# lizard-ttl-register-4bit.net
KiCad netlist of a schematic drawn in EAGLE
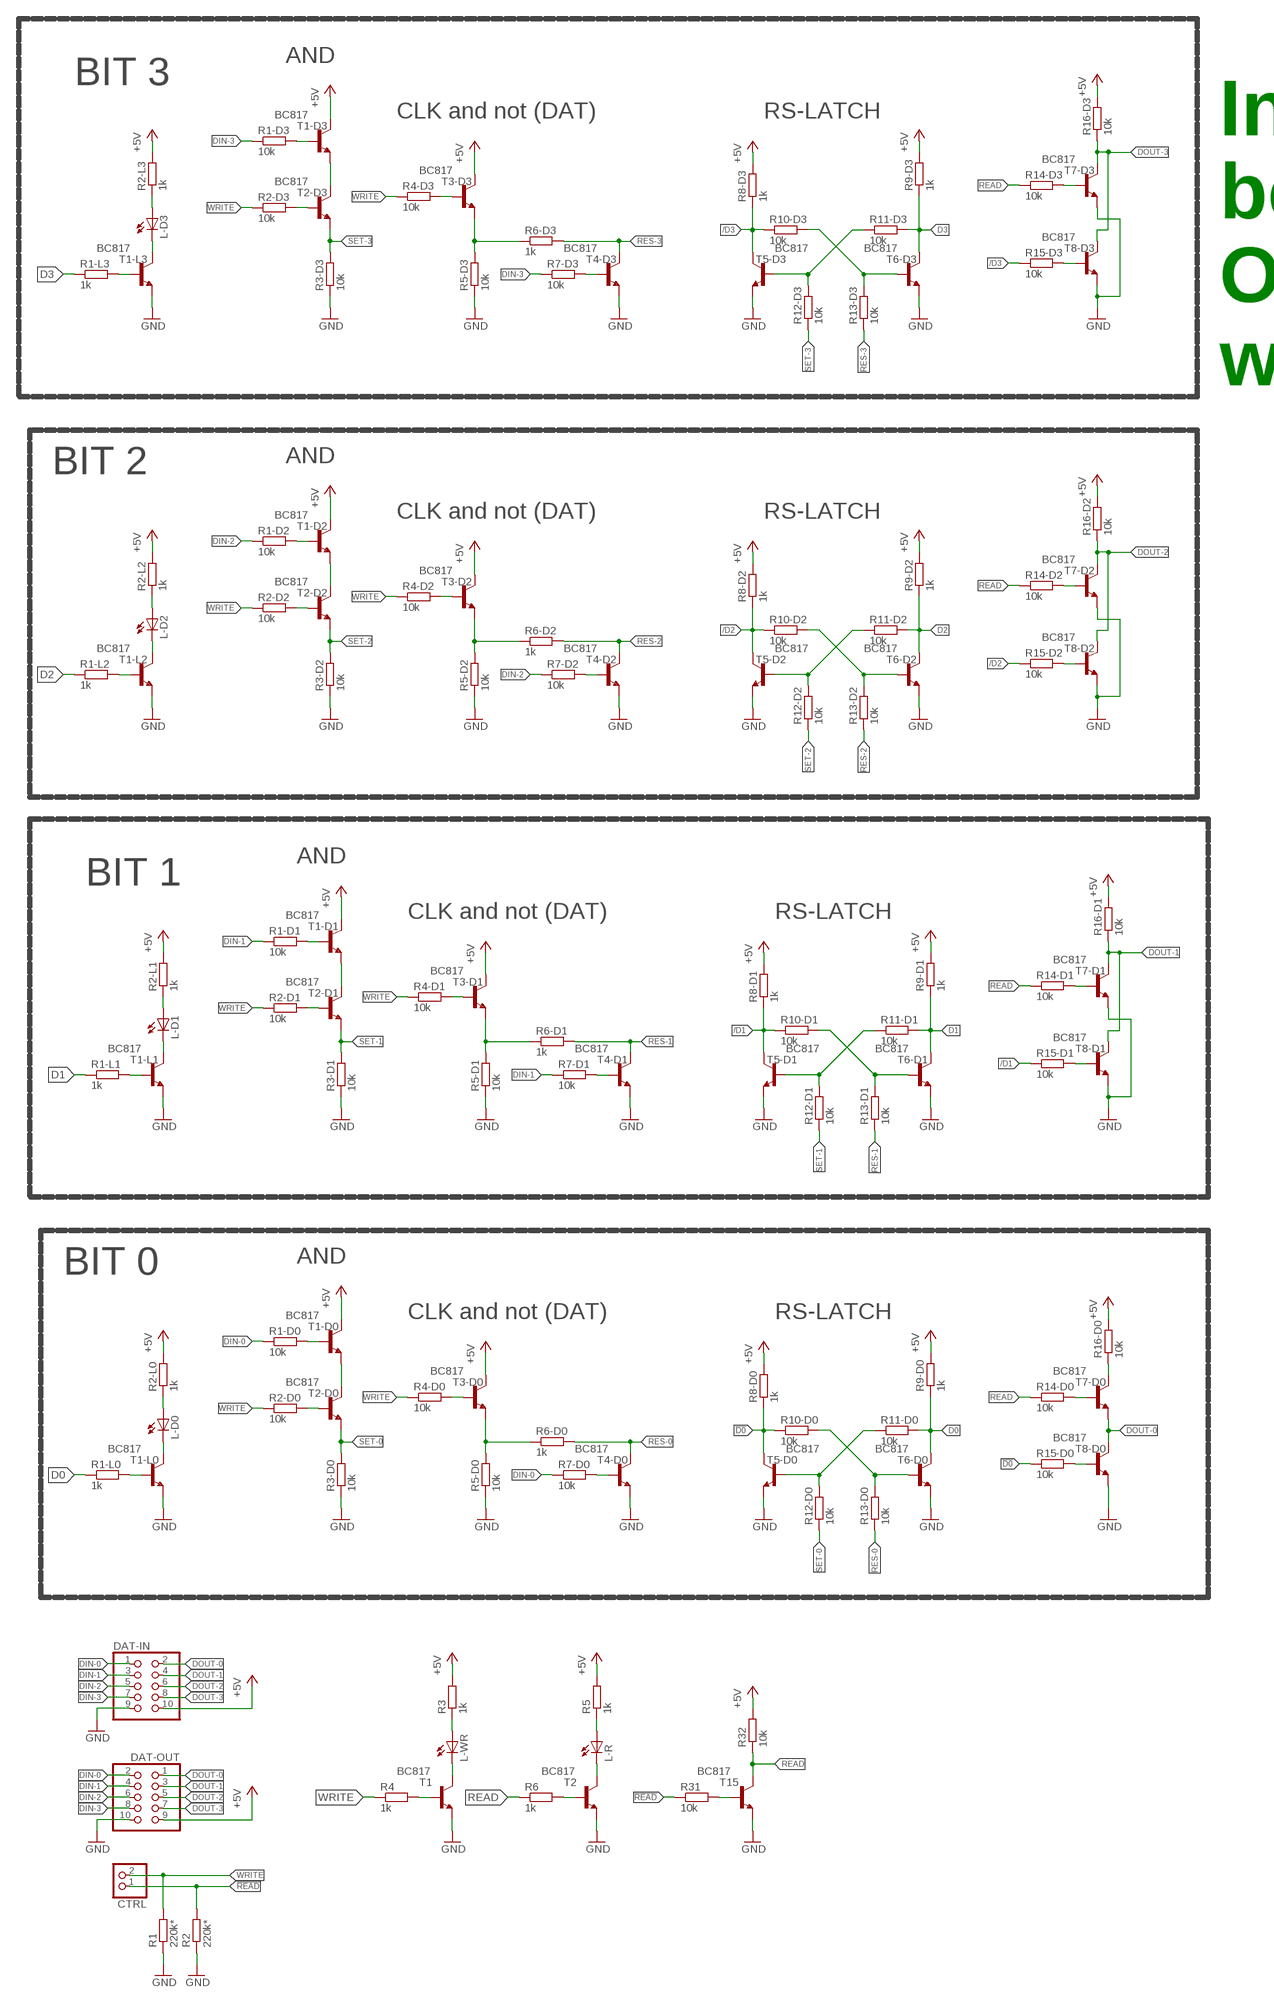
[diagram p0: schematic, sheet 1, part 1 of 2]
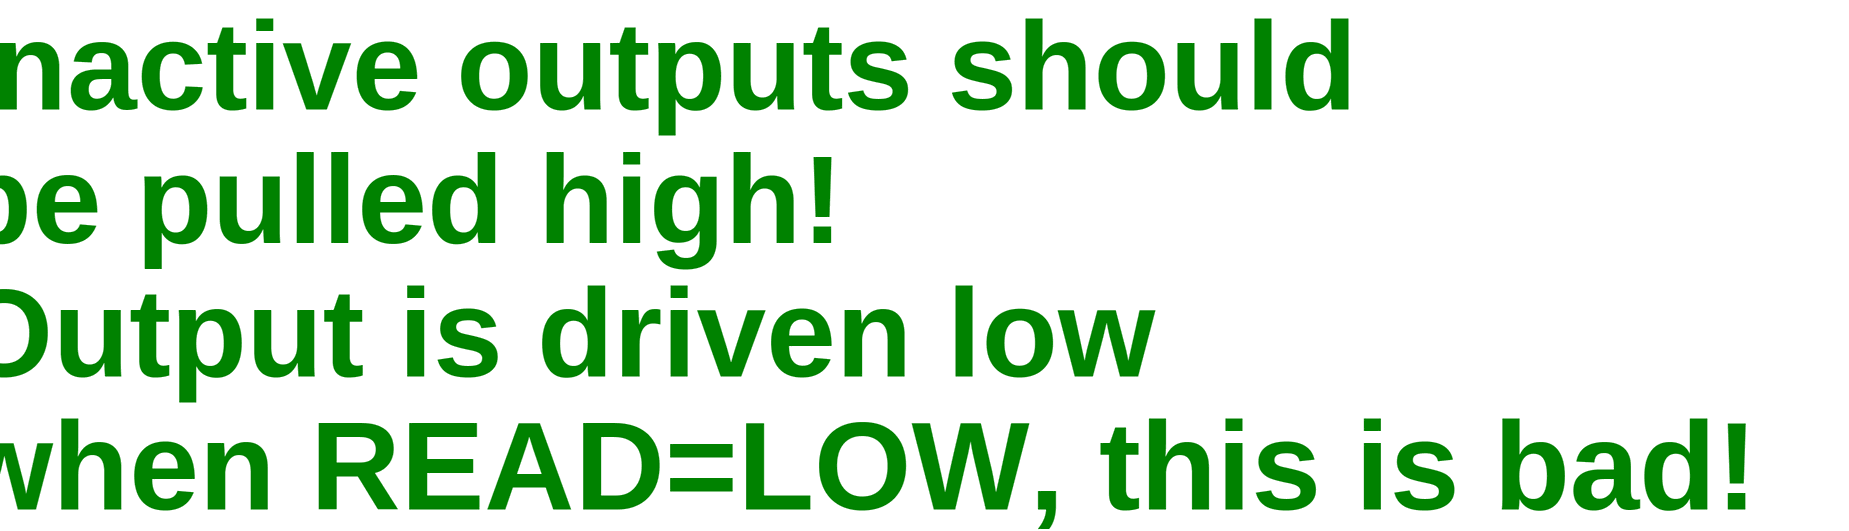
[diagram p1: schematic, sheet 1, part 2 of 2]

(export (version "E")
  (design (tool "Eeschema 10.0.6"))
  (components
    (comp (ref "CTRL")
      (value "PINHD-1X2")
      (footprint "eagle-import:1X02")
      (libsource (lib "eagle-import") (part "PINHD-1X2"))
    )
    (comp (ref "DAT-IN")
      (value "PINHD-2X5EDGE")
      (footprint "eagle-import:2X05_EDGE")
      (libsource (lib "eagle-import") (part "PINHD-2X5EDGE"))
    )
    (comp (ref "DAT-OUT")
      (value "PINHD-2X5EDGE")
      (footprint "eagle-import:2X05_EDGE")
      (libsource (lib "eagle-import") (part "PINHD-2X5EDGE"))
    )
    (comp (ref "L-D0")
      (value "LEDCHIPLED_0603")
      (footprint "eagle-import:CHIPLED_0603")
      (libsource (lib "eagle-import") (part "LEDCHIPLED_0603"))
    )
    (comp (ref "L-D1")
      (value "LEDCHIPLED_0603")
      (footprint "eagle-import:CHIPLED_0603")
      (libsource (lib "eagle-import") (part "LEDCHIPLED_0603"))
    )
    (comp (ref "L-D2")
      (value "LEDCHIPLED_0603")
      (footprint "eagle-import:CHIPLED_0603")
      (libsource (lib "eagle-import") (part "LEDCHIPLED_0603"))
    )
    (comp (ref "L-D3")
      (value "LEDCHIPLED_0603")
      (footprint "eagle-import:CHIPLED_0603")
      (libsource (lib "eagle-import") (part "LEDCHIPLED_0603"))
    )
    (comp (ref "L-R")
      (value "LEDCHIPLED_0603")
      (footprint "eagle-import:CHIPLED_0603")
      (libsource (lib "eagle-import") (part "LEDCHIPLED_0603"))
    )
    (comp (ref "L-WR")
      (value "LEDCHIPLED_0603")
      (footprint "eagle-import:CHIPLED_0603")
      (libsource (lib "eagle-import") (part "LEDCHIPLED_0603"))
    )
    (comp (ref "R1")
      (value "220k*")
      (footprint "eagle-import:R0603")
      (libsource (lib "eagle-import") (part "R-EU_R0603"))
    )
    (comp (ref "R1-D0")
      (value "10k")
      (footprint "eagle-import:R0603")
      (libsource (lib "eagle-import") (part "R-EU_R0603"))
    )
    (comp (ref "R1-D1")
      (value "10k")
      (footprint "eagle-import:R0603")
      (libsource (lib "eagle-import") (part "R-EU_R0603"))
    )
    (comp (ref "R1-D2")
      (value "10k")
      (footprint "eagle-import:R0603")
      (libsource (lib "eagle-import") (part "R-EU_R0603"))
    )
    (comp (ref "R1-D3")
      (value "10k")
      (footprint "eagle-import:R0603")
      (libsource (lib "eagle-import") (part "R-EU_R0603"))
    )
    (comp (ref "R1-L0")
      (value "1k")
      (footprint "eagle-import:R0603")
      (libsource (lib "eagle-import") (part "R-EU_R0603"))
    )
    (comp (ref "R1-L1")
      (value "1k")
      (footprint "eagle-import:R0603")
      (libsource (lib "eagle-import") (part "R-EU_R0603"))
    )
    (comp (ref "R1-L2")
      (value "1k")
      (footprint "eagle-import:R0603")
      (libsource (lib "eagle-import") (part "R-EU_R0603"))
    )
    (comp (ref "R1-L3")
      (value "1k")
      (footprint "eagle-import:R0603")
      (libsource (lib "eagle-import") (part "R-EU_R0603"))
    )
    (comp (ref "R2")
      (value "220k*")
      (footprint "eagle-import:R0603")
      (libsource (lib "eagle-import") (part "R-EU_R0603"))
    )
    (comp (ref "R2-D0")
      (value "10k")
      (footprint "eagle-import:R0603")
      (libsource (lib "eagle-import") (part "R-EU_R0603"))
    )
    (comp (ref "R2-D1")
      (value "10k")
      (footprint "eagle-import:R0603")
      (libsource (lib "eagle-import") (part "R-EU_R0603"))
    )
    (comp (ref "R2-D2")
      (value "10k")
      (footprint "eagle-import:R0603")
      (libsource (lib "eagle-import") (part "R-EU_R0603"))
    )
    (comp (ref "R2-D3")
      (value "10k")
      (footprint "eagle-import:R0603")
      (libsource (lib "eagle-import") (part "R-EU_R0603"))
    )
    (comp (ref "R2-L0")
      (value "1k")
      (footprint "eagle-import:R0603")
      (libsource (lib "eagle-import") (part "R-EU_R0603"))
    )
    (comp (ref "R2-L1")
      (value "1k")
      (footprint "eagle-import:R0603")
      (libsource (lib "eagle-import") (part "R-EU_R0603"))
    )
    (comp (ref "R2-L2")
      (value "1k")
      (footprint "eagle-import:R0603")
      (libsource (lib "eagle-import") (part "R-EU_R0603"))
    )
    (comp (ref "R2-L3")
      (value "1k")
      (footprint "eagle-import:R0603")
      (libsource (lib "eagle-import") (part "R-EU_R0603"))
    )
    (comp (ref "R3")
      (value "1k")
      (footprint "eagle-import:R0603")
      (libsource (lib "eagle-import") (part "R-EU_R0603"))
    )
    (comp (ref "R3-D0")
      (value "10k")
      (footprint "eagle-import:R0603")
      (libsource (lib "eagle-import") (part "R-EU_R0603"))
    )
    (comp (ref "R3-D1")
      (value "10k")
      (footprint "eagle-import:R0603")
      (libsource (lib "eagle-import") (part "R-EU_R0603"))
    )
    (comp (ref "R3-D2")
      (value "10k")
      (footprint "eagle-import:R0603")
      (libsource (lib "eagle-import") (part "R-EU_R0603"))
    )
    (comp (ref "R3-D3")
      (value "10k")
      (footprint "eagle-import:R0603")
      (libsource (lib "eagle-import") (part "R-EU_R0603"))
    )
    (comp (ref "R4")
      (value "1k")
      (footprint "eagle-import:R0603")
      (libsource (lib "eagle-import") (part "R-EU_R0603"))
    )
    (comp (ref "R4-D0")
      (value "10k")
      (footprint "eagle-import:R0603")
      (libsource (lib "eagle-import") (part "R-EU_R0603"))
    )
    (comp (ref "R4-D1")
      (value "10k")
      (footprint "eagle-import:R0603")
      (libsource (lib "eagle-import") (part "R-EU_R0603"))
    )
    (comp (ref "R4-D2")
      (value "10k")
      (footprint "eagle-import:R0603")
      (libsource (lib "eagle-import") (part "R-EU_R0603"))
    )
    (comp (ref "R4-D3")
      (value "10k")
      (footprint "eagle-import:R0603")
      (libsource (lib "eagle-import") (part "R-EU_R0603"))
    )
    (comp (ref "R5")
      (value "1k")
      (footprint "eagle-import:R0603")
      (libsource (lib "eagle-import") (part "R-EU_R0603"))
    )
    (comp (ref "R5-D0")
      (value "10k")
      (footprint "eagle-import:R0603")
      (libsource (lib "eagle-import") (part "R-EU_R0603"))
    )
    (comp (ref "R5-D1")
      (value "10k")
      (footprint "eagle-import:R0603")
      (libsource (lib "eagle-import") (part "R-EU_R0603"))
    )
    (comp (ref "R5-D2")
      (value "10k")
      (footprint "eagle-import:R0603")
      (libsource (lib "eagle-import") (part "R-EU_R0603"))
    )
    (comp (ref "R5-D3")
      (value "10k")
      (footprint "eagle-import:R0603")
      (libsource (lib "eagle-import") (part "R-EU_R0603"))
    )
    (comp (ref "R6")
      (value "1k")
      (footprint "eagle-import:R0603")
      (libsource (lib "eagle-import") (part "R-EU_R0603"))
    )
    (comp (ref "R6-D0")
      (value "1k")
      (footprint "eagle-import:R0603")
      (libsource (lib "eagle-import") (part "R-EU_R0603"))
    )
    (comp (ref "R6-D1")
      (value "1k")
      (footprint "eagle-import:R0603")
      (libsource (lib "eagle-import") (part "R-EU_R0603"))
    )
    (comp (ref "R6-D2")
      (value "1k")
      (footprint "eagle-import:R0603")
      (libsource (lib "eagle-import") (part "R-EU_R0603"))
    )
    (comp (ref "R6-D3")
      (value "1k")
      (footprint "eagle-import:R0603")
      (libsource (lib "eagle-import") (part "R-EU_R0603"))
    )
    (comp (ref "R7-D0")
      (value "10k")
      (footprint "eagle-import:R0603")
      (libsource (lib "eagle-import") (part "R-EU_R0603"))
    )
    (comp (ref "R7-D1")
      (value "10k")
      (footprint "eagle-import:R0603")
      (libsource (lib "eagle-import") (part "R-EU_R0603"))
    )
    (comp (ref "R7-D2")
      (value "10k")
      (footprint "eagle-import:R0603")
      (libsource (lib "eagle-import") (part "R-EU_R0603"))
    )
    (comp (ref "R7-D3")
      (value "10k")
      (footprint "eagle-import:R0603")
      (libsource (lib "eagle-import") (part "R-EU_R0603"))
    )
    (comp (ref "R8-D0")
      (value "1k")
      (footprint "eagle-import:R0603")
      (libsource (lib "eagle-import") (part "R-EU_R0603"))
    )
    (comp (ref "R8-D1")
      (value "1k")
      (footprint "eagle-import:R0603")
      (libsource (lib "eagle-import") (part "R-EU_R0603"))
    )
    (comp (ref "R8-D2")
      (value "1k")
      (footprint "eagle-import:R0603")
      (libsource (lib "eagle-import") (part "R-EU_R0603"))
    )
    (comp (ref "R8-D3")
      (value "1k")
      (footprint "eagle-import:R0603")
      (libsource (lib "eagle-import") (part "R-EU_R0603"))
    )
    (comp (ref "R9-D0")
      (value "1k")
      (footprint "eagle-import:R0603")
      (libsource (lib "eagle-import") (part "R-EU_R0603"))
    )
    (comp (ref "R9-D1")
      (value "1k")
      (footprint "eagle-import:R0603")
      (libsource (lib "eagle-import") (part "R-EU_R0603"))
    )
    (comp (ref "R9-D2")
      (value "1k")
      (footprint "eagle-import:R0603")
      (libsource (lib "eagle-import") (part "R-EU_R0603"))
    )
    (comp (ref "R9-D3")
      (value "1k")
      (footprint "eagle-import:R0603")
      (libsource (lib "eagle-import") (part "R-EU_R0603"))
    )
    (comp (ref "R10-D0")
      (value "10k")
      (footprint "eagle-import:R0603")
      (libsource (lib "eagle-import") (part "R-EU_R0603"))
    )
    (comp (ref "R10-D1")
      (value "10k")
      (footprint "eagle-import:R0603")
      (libsource (lib "eagle-import") (part "R-EU_R0603"))
    )
    (comp (ref "R10-D2")
      (value "10k")
      (footprint "eagle-import:R0603")
      (libsource (lib "eagle-import") (part "R-EU_R0603"))
    )
    (comp (ref "R10-D3")
      (value "10k")
      (footprint "eagle-import:R0603")
      (libsource (lib "eagle-import") (part "R-EU_R0603"))
    )
    (comp (ref "R11-D0")
      (value "10k")
      (footprint "eagle-import:R0603")
      (libsource (lib "eagle-import") (part "R-EU_R0603"))
    )
    (comp (ref "R11-D1")
      (value "10k")
      (footprint "eagle-import:R0603")
      (libsource (lib "eagle-import") (part "R-EU_R0603"))
    )
    (comp (ref "R11-D2")
      (value "10k")
      (footprint "eagle-import:R0603")
      (libsource (lib "eagle-import") (part "R-EU_R0603"))
    )
    (comp (ref "R11-D3")
      (value "10k")
      (footprint "eagle-import:R0603")
      (libsource (lib "eagle-import") (part "R-EU_R0603"))
    )
    (comp (ref "R12-D0")
      (value "10k")
      (footprint "eagle-import:R0603")
      (libsource (lib "eagle-import") (part "R-EU_R0603"))
    )
    (comp (ref "R12-D1")
      (value "10k")
      (footprint "eagle-import:R0603")
      (libsource (lib "eagle-import") (part "R-EU_R0603"))
    )
    (comp (ref "R12-D2")
      (value "10k")
      (footprint "eagle-import:R0603")
      (libsource (lib "eagle-import") (part "R-EU_R0603"))
    )
    (comp (ref "R12-D3")
      (value "10k")
      (footprint "eagle-import:R0603")
      (libsource (lib "eagle-import") (part "R-EU_R0603"))
    )
    (comp (ref "R13-D0")
      (value "10k")
      (footprint "eagle-import:R0603")
      (libsource (lib "eagle-import") (part "R-EU_R0603"))
    )
    (comp (ref "R13-D1")
      (value "10k")
      (footprint "eagle-import:R0603")
      (libsource (lib "eagle-import") (part "R-EU_R0603"))
    )
    (comp (ref "R13-D2")
      (value "10k")
      (footprint "eagle-import:R0603")
      (libsource (lib "eagle-import") (part "R-EU_R0603"))
    )
    (comp (ref "R13-D3")
      (value "10k")
      (footprint "eagle-import:R0603")
      (libsource (lib "eagle-import") (part "R-EU_R0603"))
    )
    (comp (ref "R14-D0")
      (value "10k")
      (footprint "eagle-import:R0603")
      (libsource (lib "eagle-import") (part "R-EU_R0603"))
    )
    (comp (ref "R14-D1")
      (value "10k")
      (footprint "eagle-import:R0603")
      (libsource (lib "eagle-import") (part "R-EU_R0603"))
    )
    (comp (ref "R14-D2")
      (value "10k")
      (footprint "eagle-import:R0603")
      (libsource (lib "eagle-import") (part "R-EU_R0603"))
    )
    (comp (ref "R14-D3")
      (value "10k")
      (footprint "eagle-import:R0603")
      (libsource (lib "eagle-import") (part "R-EU_R0603"))
    )
    (comp (ref "R15-D0")
      (value "10k")
      (footprint "eagle-import:R0603")
      (libsource (lib "eagle-import") (part "R-EU_R0603"))
    )
    (comp (ref "R15-D1")
      (value "10k")
      (footprint "eagle-import:R0603")
      (libsource (lib "eagle-import") (part "R-EU_R0603"))
    )
    (comp (ref "R15-D2")
      (value "10k")
      (footprint "eagle-import:R0603")
      (libsource (lib "eagle-import") (part "R-EU_R0603"))
    )
    (comp (ref "R15-D3")
      (value "10k")
      (footprint "eagle-import:R0603")
      (libsource (lib "eagle-import") (part "R-EU_R0603"))
    )
    (comp (ref "R16-D0")
      (value "10k")
      (footprint "eagle-import:R0603")
      (libsource (lib "eagle-import") (part "R-EU_R0603"))
    )
    (comp (ref "R16-D1")
      (value "10k")
      (footprint "eagle-import:R0603")
      (libsource (lib "eagle-import") (part "R-EU_R0603"))
    )
    (comp (ref "R16-D2")
      (value "10k")
      (footprint "eagle-import:R0603")
      (libsource (lib "eagle-import") (part "R-EU_R0603"))
    )
    (comp (ref "R16-D3")
      (value "10k")
      (footprint "eagle-import:R0603")
      (libsource (lib "eagle-import") (part "R-EU_R0603"))
    )
    (comp (ref "R31")
      (value "10k")
      (footprint "eagle-import:R0603")
      (libsource (lib "eagle-import") (part "R-EU_R0603"))
    )
    (comp (ref "R32")
      (value "10k")
      (footprint "eagle-import:R0603")
      (libsource (lib "eagle-import") (part "R-EU_R0603"))
    )
    (comp (ref "T1")
      (value "BC817")
      (footprint "eagle-import:SOT23-BEC")
      (libsource (lib "eagle-import") (part "-NPN-SOT23-BECBC817-40"))
    )
    (comp (ref "T1-D0")
      (value "BC817")
      (footprint "eagle-import:SOT23-BEC")
      (libsource (lib "eagle-import") (part "-NPN-SOT23-BECBC817-40"))
    )
    (comp (ref "T1-D1")
      (value "BC817")
      (footprint "eagle-import:SOT23-BEC")
      (libsource (lib "eagle-import") (part "-NPN-SOT23-BECBC817-40"))
    )
    (comp (ref "T1-D2")
      (value "BC817")
      (footprint "eagle-import:SOT23-BEC")
      (libsource (lib "eagle-import") (part "-NPN-SOT23-BECBC817-40"))
    )
    (comp (ref "T1-D3")
      (value "BC817")
      (footprint "eagle-import:SOT23-BEC")
      (libsource (lib "eagle-import") (part "-NPN-SOT23-BECBC817-40"))
    )
    (comp (ref "T1-L0")
      (value "BC817")
      (footprint "eagle-import:SOT23-BEC")
      (libsource (lib "eagle-import") (part "-NPN-SOT23-BECBC817-40"))
    )
    (comp (ref "T1-L1")
      (value "BC817")
      (footprint "eagle-import:SOT23-BEC")
      (libsource (lib "eagle-import") (part "-NPN-SOT23-BECBC817-40"))
    )
    (comp (ref "T1-L2")
      (value "BC817")
      (footprint "eagle-import:SOT23-BEC")
      (libsource (lib "eagle-import") (part "-NPN-SOT23-BECBC817-40"))
    )
    (comp (ref "T1-L3")
      (value "BC817")
      (footprint "eagle-import:SOT23-BEC")
      (libsource (lib "eagle-import") (part "-NPN-SOT23-BECBC817-40"))
    )
    (comp (ref "T2")
      (value "BC817")
      (footprint "eagle-import:SOT23-BEC")
      (libsource (lib "eagle-import") (part "-NPN-SOT23-BECBC817-40"))
    )
    (comp (ref "T2-D0")
      (value "BC817")
      (footprint "eagle-import:SOT23-BEC")
      (libsource (lib "eagle-import") (part "-NPN-SOT23-BECBC817-40"))
    )
    (comp (ref "T2-D1")
      (value "BC817")
      (footprint "eagle-import:SOT23-BEC")
      (libsource (lib "eagle-import") (part "-NPN-SOT23-BECBC817-40"))
    )
    (comp (ref "T2-D2")
      (value "BC817")
      (footprint "eagle-import:SOT23-BEC")
      (libsource (lib "eagle-import") (part "-NPN-SOT23-BECBC817-40"))
    )
    (comp (ref "T2-D3")
      (value "BC817")
      (footprint "eagle-import:SOT23-BEC")
      (libsource (lib "eagle-import") (part "-NPN-SOT23-BECBC817-40"))
    )
    (comp (ref "T3-D0")
      (value "BC817")
      (footprint "eagle-import:SOT23-BEC")
      (libsource (lib "eagle-import") (part "-NPN-SOT23-BECBC817-40"))
    )
    (comp (ref "T3-D1")
      (value "BC817")
      (footprint "eagle-import:SOT23-BEC")
      (libsource (lib "eagle-import") (part "-NPN-SOT23-BECBC817-40"))
    )
    (comp (ref "T3-D2")
      (value "BC817")
      (footprint "eagle-import:SOT23-BEC")
      (libsource (lib "eagle-import") (part "-NPN-SOT23-BECBC817-40"))
    )
    (comp (ref "T3-D3")
      (value "BC817")
      (footprint "eagle-import:SOT23-BEC")
      (libsource (lib "eagle-import") (part "-NPN-SOT23-BECBC817-40"))
    )
    (comp (ref "T4-D0")
      (value "BC817")
      (footprint "eagle-import:SOT23-BEC")
      (libsource (lib "eagle-import") (part "-NPN-SOT23-BECBC817-40"))
    )
    (comp (ref "T4-D1")
      (value "BC817")
      (footprint "eagle-import:SOT23-BEC")
      (libsource (lib "eagle-import") (part "-NPN-SOT23-BECBC817-40"))
    )
    (comp (ref "T4-D2")
      (value "BC817")
      (footprint "eagle-import:SOT23-BEC")
      (libsource (lib "eagle-import") (part "-NPN-SOT23-BECBC817-40"))
    )
    (comp (ref "T4-D3")
      (value "BC817")
      (footprint "eagle-import:SOT23-BEC")
      (libsource (lib "eagle-import") (part "-NPN-SOT23-BECBC817-40"))
    )
    (comp (ref "T5-D0")
      (value "BC817")
      (footprint "eagle-import:SOT23-BEC")
      (libsource (lib "eagle-import") (part "-NPN-SOT23-BECBC817-40"))
    )
    (comp (ref "T5-D1")
      (value "BC817")
      (footprint "eagle-import:SOT23-BEC")
      (libsource (lib "eagle-import") (part "-NPN-SOT23-BECBC817-40"))
    )
    (comp (ref "T5-D2")
      (value "BC817")
      (footprint "eagle-import:SOT23-BEC")
      (libsource (lib "eagle-import") (part "-NPN-SOT23-BECBC817-40"))
    )
    (comp (ref "T5-D3")
      (value "BC817")
      (footprint "eagle-import:SOT23-BEC")
      (libsource (lib "eagle-import") (part "-NPN-SOT23-BECBC817-40"))
    )
    (comp (ref "T6-D0")
      (value "BC817")
      (footprint "eagle-import:SOT23-BEC")
      (libsource (lib "eagle-import") (part "-NPN-SOT23-BECBC817-40"))
    )
    (comp (ref "T6-D1")
      (value "BC817")
      (footprint "eagle-import:SOT23-BEC")
      (libsource (lib "eagle-import") (part "-NPN-SOT23-BECBC817-40"))
    )
    (comp (ref "T6-D2")
      (value "BC817")
      (footprint "eagle-import:SOT23-BEC")
      (libsource (lib "eagle-import") (part "-NPN-SOT23-BECBC817-40"))
    )
    (comp (ref "T6-D3")
      (value "BC817")
      (footprint "eagle-import:SOT23-BEC")
      (libsource (lib "eagle-import") (part "-NPN-SOT23-BECBC817-40"))
    )
    (comp (ref "T7-D0")
      (value "BC817")
      (footprint "eagle-import:SOT23-BEC")
      (libsource (lib "eagle-import") (part "-NPN-SOT23-BECBC817-40"))
    )
    (comp (ref "T7-D1")
      (value "BC817")
      (footprint "eagle-import:SOT23-BEC")
      (libsource (lib "eagle-import") (part "-NPN-SOT23-BECBC817-40"))
    )
    (comp (ref "T7-D2")
      (value "BC817")
      (footprint "eagle-import:SOT23-BEC")
      (libsource (lib "eagle-import") (part "-NPN-SOT23-BECBC817-40"))
    )
    (comp (ref "T7-D3")
      (value "BC817")
      (footprint "eagle-import:SOT23-BEC")
      (libsource (lib "eagle-import") (part "-NPN-SOT23-BECBC817-40"))
    )
    (comp (ref "T8-D0")
      (value "BC817")
      (footprint "eagle-import:SOT23-BEC")
      (libsource (lib "eagle-import") (part "-NPN-SOT23-BECBC817-40"))
    )
    (comp (ref "T8-D1")
      (value "BC817")
      (footprint "eagle-import:SOT23-BEC")
      (libsource (lib "eagle-import") (part "-NPN-SOT23-BECBC817-40"))
    )
    (comp (ref "T8-D2")
      (value "BC817")
      (footprint "eagle-import:SOT23-BEC")
      (libsource (lib "eagle-import") (part "-NPN-SOT23-BECBC817-40"))
    )
    (comp (ref "T8-D3")
      (value "BC817")
      (footprint "eagle-import:SOT23-BEC")
      (libsource (lib "eagle-import") (part "-NPN-SOT23-BECBC817-40"))
    )
    (comp (ref "T15")
      (value "BC817")
      (footprint "eagle-import:SOT23-BEC")
      (libsource (lib "eagle-import") (part "-NPN-SOT23-BECBC817-40"))
    )
  )
  (nets
    (net (code "1") (name "+5V") (class "Default")
      (node (ref "DAT-IN") (pin "10") (pinfunction "10_10") (pintype "passive"))
      (node (ref "DAT-OUT") (pin "9") (pinfunction "9_9") (pintype "passive"))
      (node (ref "R16-D0") (pin "2") (pinfunction "2_2") (pintype "passive"))
      (node (ref "R16-D1") (pin "2") (pinfunction "2_2") (pintype "passive"))
      (node (ref "R16-D2") (pin "2") (pinfunction "2_2") (pintype "passive"))
      (node (ref "R16-D3") (pin "2") (pinfunction "2_2") (pintype "passive"))
      (node (ref "R2-L0") (pin "2") (pinfunction "2_2") (pintype "passive"))
      (node (ref "R2-L1") (pin "2") (pinfunction "2_2") (pintype "passive"))
      (node (ref "R2-L2") (pin "2") (pinfunction "2_2") (pintype "passive"))
      (node (ref "R2-L3") (pin "2") (pinfunction "2_2") (pintype "passive"))
      (node (ref "R3") (pin "2") (pinfunction "2_2") (pintype "passive"))
      (node (ref "R32") (pin "2") (pinfunction "2_2") (pintype "passive"))
      (node (ref "R5") (pin "2") (pinfunction "2_2") (pintype "passive"))
      (node (ref "R8-D0") (pin "2") (pinfunction "2_2") (pintype "passive"))
      (node (ref "R8-D1") (pin "2") (pinfunction "2_2") (pintype "passive"))
      (node (ref "R8-D2") (pin "2") (pinfunction "2_2") (pintype "passive"))
      (node (ref "R8-D3") (pin "2") (pinfunction "2_2") (pintype "passive"))
      (node (ref "R9-D0") (pin "2") (pinfunction "2_2") (pintype "passive"))
      (node (ref "R9-D1") (pin "2") (pinfunction "2_2") (pintype "passive"))
      (node (ref "R9-D2") (pin "2") (pinfunction "2_2") (pintype "passive"))
      (node (ref "R9-D3") (pin "2") (pinfunction "2_2") (pintype "passive"))
      (node (ref "T1-D0") (pin "C") (pinfunction "C_C") (pintype "passive"))
      (node (ref "T1-D1") (pin "C") (pinfunction "C_C") (pintype "passive"))
      (node (ref "T1-D2") (pin "C") (pinfunction "C_C") (pintype "passive"))
      (node (ref "T1-D3") (pin "C") (pinfunction "C_C") (pintype "passive"))
      (node (ref "T3-D0") (pin "C") (pinfunction "C_C") (pintype "passive"))
      (node (ref "T3-D1") (pin "C") (pinfunction "C_C") (pintype "passive"))
      (node (ref "T3-D2") (pin "C") (pinfunction "C_C") (pintype "passive"))
      (node (ref "T3-D3") (pin "C") (pinfunction "C_C") (pintype "passive"))
    )
    (net (code "2") (name "/~{D0}") (class "Default")
      (node (ref "R10-D0") (pin "1") (pinfunction "1_1") (pintype "passive"))
      (node (ref "R15-D0") (pin "1") (pinfunction "1_1") (pintype "passive"))
      (node (ref "R8-D0") (pin "1") (pinfunction "1_1") (pintype "passive"))
      (node (ref "T5-D0") (pin "C") (pinfunction "C_C") (pintype "passive"))
    )
    (net (code "3") (name "/~{READ}") (class "Default")
      (node (ref "CTRL") (pin "1") (pinfunction "1_1") (pintype "passive"))
      (node (ref "R2") (pin "2") (pinfunction "2_2") (pintype "passive"))
      (node (ref "R31") (pin "1") (pinfunction "1_1") (pintype "passive"))
    )
    (net (code "4") (name "D0") (class "Default")
      (node (ref "R1-L0") (pin "1") (pinfunction "1_1") (pintype "passive"))
      (node (ref "R11-D0") (pin "2") (pinfunction "2_2") (pintype "passive"))
      (node (ref "R9-D0") (pin "1") (pinfunction "1_1") (pintype "passive"))
      (node (ref "T6-D0") (pin "C") (pinfunction "C_C") (pintype "passive"))
    )
    (net (code "5") (name "D1") (class "Default")
      (node (ref "R1-L1") (pin "1") (pinfunction "1_1") (pintype "passive"))
      (node (ref "R11-D1") (pin "2") (pinfunction "2_2") (pintype "passive"))
      (node (ref "R9-D1") (pin "1") (pinfunction "1_1") (pintype "passive"))
      (node (ref "T6-D1") (pin "C") (pinfunction "C_C") (pintype "passive"))
    )
    (net (code "6") (name "D2") (class "Default")
      (node (ref "R1-L2") (pin "1") (pinfunction "1_1") (pintype "passive"))
      (node (ref "R11-D2") (pin "2") (pinfunction "2_2") (pintype "passive"))
      (node (ref "R9-D2") (pin "1") (pinfunction "1_1") (pintype "passive"))
      (node (ref "T6-D2") (pin "C") (pinfunction "C_C") (pintype "passive"))
    )
    (net (code "7") (name "D3") (class "Default")
      (node (ref "R1-L3") (pin "1") (pinfunction "1_1") (pintype "passive"))
      (node (ref "R11-D3") (pin "2") (pinfunction "2_2") (pintype "passive"))
      (node (ref "R9-D3") (pin "1") (pinfunction "1_1") (pintype "passive"))
      (node (ref "T6-D3") (pin "C") (pinfunction "C_C") (pintype "passive"))
    )
    (net (code "8") (name "DIN-0") (class "Default")
      (node (ref "DAT-IN") (pin "1") (pinfunction "1_1") (pintype "passive"))
      (node (ref "DAT-OUT") (pin "2") (pinfunction "2_2") (pintype "passive"))
      (node (ref "R1-D0") (pin "1") (pinfunction "1_1") (pintype "passive"))
      (node (ref "R7-D0") (pin "1") (pinfunction "1_1") (pintype "passive"))
    )
    (net (code "9") (name "DIN-1") (class "Default")
      (node (ref "DAT-IN") (pin "3") (pinfunction "3_3") (pintype "passive"))
      (node (ref "DAT-OUT") (pin "4") (pinfunction "4_4") (pintype "passive"))
      (node (ref "R1-D1") (pin "1") (pinfunction "1_1") (pintype "passive"))
      (node (ref "R7-D1") (pin "1") (pinfunction "1_1") (pintype "passive"))
    )
    (net (code "10") (name "DIN-2") (class "Default")
      (node (ref "DAT-IN") (pin "5") (pinfunction "5_5") (pintype "passive"))
      (node (ref "DAT-OUT") (pin "6") (pinfunction "6_6") (pintype "passive"))
      (node (ref "R1-D2") (pin "1") (pinfunction "1_1") (pintype "passive"))
      (node (ref "R7-D2") (pin "1") (pinfunction "1_1") (pintype "passive"))
    )
    (net (code "11") (name "DIN-3") (class "Default")
      (node (ref "DAT-IN") (pin "7") (pinfunction "7_7") (pintype "passive"))
      (node (ref "DAT-OUT") (pin "8") (pinfunction "8_8") (pintype "passive"))
      (node (ref "R1-D3") (pin "1") (pinfunction "1_1") (pintype "passive"))
      (node (ref "R7-D3") (pin "1") (pinfunction "1_1") (pintype "passive"))
    )
    (net (code "12") (name "DOUT-0") (class "Default")
      (node (ref "DAT-IN") (pin "2") (pinfunction "2_2") (pintype "passive"))
      (node (ref "DAT-OUT") (pin "1") (pinfunction "1_1") (pintype "passive"))
      (node (ref "T7-D0") (pin "E") (pinfunction "E_E") (pintype "passive"))
      (node (ref "T8-D0") (pin "C") (pinfunction "C_C") (pintype "passive"))
    )
    (net (code "13") (name "DOUT-1") (class "Default")
      (node (ref "DAT-IN") (pin "4") (pinfunction "4_4") (pintype "passive"))
      (node (ref "DAT-OUT") (pin "3") (pinfunction "3_3") (pintype "passive"))
      (node (ref "R16-D1") (pin "1") (pinfunction "1_1") (pintype "passive"))
      (node (ref "T7-D1") (pin "C") (pinfunction "C_C") (pintype "passive"))
      (node (ref "T8-D1") (pin "C") (pinfunction "C_C") (pintype "passive"))
    )
    (net (code "14") (name "DOUT-2") (class "Default")
      (node (ref "DAT-IN") (pin "6") (pinfunction "6_6") (pintype "passive"))
      (node (ref "DAT-OUT") (pin "5") (pinfunction "5_5") (pintype "passive"))
      (node (ref "R16-D2") (pin "1") (pinfunction "1_1") (pintype "passive"))
      (node (ref "T7-D2") (pin "C") (pinfunction "C_C") (pintype "passive"))
      (node (ref "T8-D2") (pin "C") (pinfunction "C_C") (pintype "passive"))
    )
    (net (code "15") (name "DOUT-3") (class "Default")
      (node (ref "DAT-IN") (pin "8") (pinfunction "8_8") (pintype "passive"))
      (node (ref "DAT-OUT") (pin "7") (pinfunction "7_7") (pintype "passive"))
      (node (ref "R16-D3") (pin "1") (pinfunction "1_1") (pintype "passive"))
      (node (ref "T7-D3") (pin "C") (pinfunction "C_C") (pintype "passive"))
      (node (ref "T8-D3") (pin "C") (pinfunction "C_C") (pintype "passive"))
    )
    (net (code "16") (name "GND") (class "Default")
      (node (ref "DAT-IN") (pin "9") (pinfunction "9_9") (pintype "passive"))
      (node (ref "DAT-OUT") (pin "10") (pinfunction "10_10") (pintype "passive"))
      (node (ref "R1") (pin "1") (pinfunction "1_1") (pintype "passive"))
      (node (ref "R2") (pin "1") (pinfunction "1_1") (pintype "passive"))
      (node (ref "R3-D0") (pin "1") (pinfunction "1_1") (pintype "passive"))
      (node (ref "R3-D1") (pin "1") (pinfunction "1_1") (pintype "passive"))
      (node (ref "R3-D2") (pin "1") (pinfunction "1_1") (pintype "passive"))
      (node (ref "R3-D3") (pin "1") (pinfunction "1_1") (pintype "passive"))
      (node (ref "R5-D0") (pin "1") (pinfunction "1_1") (pintype "passive"))
      (node (ref "R5-D1") (pin "1") (pinfunction "1_1") (pintype "passive"))
      (node (ref "R5-D2") (pin "1") (pinfunction "1_1") (pintype "passive"))
      (node (ref "R5-D3") (pin "1") (pinfunction "1_1") (pintype "passive"))
      (node (ref "T1") (pin "E") (pinfunction "E_E") (pintype "passive"))
      (node (ref "T1-L0") (pin "E") (pinfunction "E_E") (pintype "passive"))
      (node (ref "T1-L1") (pin "E") (pinfunction "E_E") (pintype "passive"))
      (node (ref "T1-L2") (pin "E") (pinfunction "E_E") (pintype "passive"))
      (node (ref "T1-L3") (pin "E") (pinfunction "E_E") (pintype "passive"))
      (node (ref "T15") (pin "E") (pinfunction "E_E") (pintype "passive"))
      (node (ref "T2") (pin "E") (pinfunction "E_E") (pintype "passive"))
      (node (ref "T4-D0") (pin "E") (pinfunction "E_E") (pintype "passive"))
      (node (ref "T4-D1") (pin "E") (pinfunction "E_E") (pintype "passive"))
      (node (ref "T4-D2") (pin "E") (pinfunction "E_E") (pintype "passive"))
      (node (ref "T4-D3") (pin "E") (pinfunction "E_E") (pintype "passive"))
      (node (ref "T5-D0") (pin "E") (pinfunction "E_E") (pintype "passive"))
      (node (ref "T5-D1") (pin "E") (pinfunction "E_E") (pintype "passive"))
      (node (ref "T5-D2") (pin "E") (pinfunction "E_E") (pintype "passive"))
      (node (ref "T5-D3") (pin "E") (pinfunction "E_E") (pintype "passive"))
      (node (ref "T6-D0") (pin "E") (pinfunction "E_E") (pintype "passive"))
      (node (ref "T6-D1") (pin "E") (pinfunction "E_E") (pintype "passive"))
      (node (ref "T6-D2") (pin "E") (pinfunction "E_E") (pintype "passive"))
      (node (ref "T6-D3") (pin "E") (pinfunction "E_E") (pintype "passive"))
      (node (ref "T7-D1") (pin "E") (pinfunction "E_E") (pintype "passive"))
      (node (ref "T7-D2") (pin "E") (pinfunction "E_E") (pintype "passive"))
      (node (ref "T7-D3") (pin "E") (pinfunction "E_E") (pintype "passive"))
      (node (ref "T8-D0") (pin "E") (pinfunction "E_E") (pintype "passive"))
      (node (ref "T8-D1") (pin "E") (pinfunction "E_E") (pintype "passive"))
      (node (ref "T8-D2") (pin "E") (pinfunction "E_E") (pintype "passive"))
      (node (ref "T8-D3") (pin "E") (pinfunction "E_E") (pintype "passive"))
    )
    (net (code "17") (name "Net-(L-D0-PadA)") (class "Default")
      (node (ref "L-D0") (pin "A") (pinfunction "A_A") (pintype "passive"))
      (node (ref "R2-L0") (pin "1") (pinfunction "1_1") (pintype "passive"))
    )
    (net (code "18") (name "Net-(L-D0-PadC)") (class "Default")
      (node (ref "L-D0") (pin "C") (pinfunction "C_C") (pintype "passive"))
      (node (ref "T1-L0") (pin "C") (pinfunction "C_C") (pintype "passive"))
    )
    (net (code "19") (name "Net-(L-D1-PadA)") (class "Default")
      (node (ref "L-D1") (pin "A") (pinfunction "A_A") (pintype "passive"))
      (node (ref "R2-L1") (pin "1") (pinfunction "1_1") (pintype "passive"))
    )
    (net (code "20") (name "Net-(L-D1-PadC)") (class "Default")
      (node (ref "L-D1") (pin "C") (pinfunction "C_C") (pintype "passive"))
      (node (ref "T1-L1") (pin "C") (pinfunction "C_C") (pintype "passive"))
    )
    (net (code "21") (name "Net-(L-D2-PadA)") (class "Default")
      (node (ref "L-D2") (pin "A") (pinfunction "A_A") (pintype "passive"))
      (node (ref "R2-L2") (pin "1") (pinfunction "1_1") (pintype "passive"))
    )
    (net (code "22") (name "Net-(L-D2-PadC)") (class "Default")
      (node (ref "L-D2") (pin "C") (pinfunction "C_C") (pintype "passive"))
      (node (ref "T1-L2") (pin "C") (pinfunction "C_C") (pintype "passive"))
    )
    (net (code "23") (name "Net-(L-D3-PadA)") (class "Default")
      (node (ref "L-D3") (pin "A") (pinfunction "A_A") (pintype "passive"))
      (node (ref "R2-L3") (pin "1") (pinfunction "1_1") (pintype "passive"))
    )
    (net (code "24") (name "Net-(L-D3-PadC)") (class "Default")
      (node (ref "L-D3") (pin "C") (pinfunction "C_C") (pintype "passive"))
      (node (ref "T1-L3") (pin "C") (pinfunction "C_C") (pintype "passive"))
    )
    (net (code "25") (name "Net-(L-R-PadA)") (class "Default")
      (node (ref "L-R") (pin "A") (pinfunction "A_A") (pintype "passive"))
      (node (ref "R5") (pin "1") (pinfunction "1_1") (pintype "passive"))
    )
    (net (code "26") (name "Net-(L-R-PadC)") (class "Default")
      (node (ref "L-R") (pin "C") (pinfunction "C_C") (pintype "passive"))
      (node (ref "T2") (pin "C") (pinfunction "C_C") (pintype "passive"))
    )
    (net (code "27") (name "Net-(L-WR-PadA)") (class "Default")
      (node (ref "L-WR") (pin "A") (pinfunction "A_A") (pintype "passive"))
      (node (ref "R3") (pin "1") (pinfunction "1_1") (pintype "passive"))
    )
    (net (code "28") (name "Net-(L-WR-PadC)") (class "Default")
      (node (ref "L-WR") (pin "C") (pinfunction "C_C") (pintype "passive"))
      (node (ref "T1") (pin "C") (pinfunction "C_C") (pintype "passive"))
    )
    (net (code "29") (name "Net-(R1-D0-Pad2)") (class "Default")
      (node (ref "R1-D0") (pin "2") (pinfunction "2_2") (pintype "passive"))
      (node (ref "T1-D0") (pin "B") (pinfunction "B_B") (pintype "passive"))
    )
    (net (code "30") (name "Net-(R1-D1-Pad2)") (class "Default")
      (node (ref "R1-D1") (pin "2") (pinfunction "2_2") (pintype "passive"))
      (node (ref "T1-D1") (pin "B") (pinfunction "B_B") (pintype "passive"))
    )
    (net (code "31") (name "Net-(R1-D2-Pad2)") (class "Default")
      (node (ref "R1-D2") (pin "2") (pinfunction "2_2") (pintype "passive"))
      (node (ref "T1-D2") (pin "B") (pinfunction "B_B") (pintype "passive"))
    )
    (net (code "32") (name "Net-(R1-D3-Pad2)") (class "Default")
      (node (ref "R1-D3") (pin "2") (pinfunction "2_2") (pintype "passive"))
      (node (ref "T1-D3") (pin "B") (pinfunction "B_B") (pintype "passive"))
    )
    (net (code "33") (name "Net-(R1-L0-Pad2)") (class "Default")
      (node (ref "R1-L0") (pin "2") (pinfunction "2_2") (pintype "passive"))
      (node (ref "T1-L0") (pin "B") (pinfunction "B_B") (pintype "passive"))
    )
    (net (code "34") (name "Net-(R1-L1-Pad2)") (class "Default")
      (node (ref "R1-L1") (pin "2") (pinfunction "2_2") (pintype "passive"))
      (node (ref "T1-L1") (pin "B") (pinfunction "B_B") (pintype "passive"))
    )
    (net (code "35") (name "Net-(R1-L2-Pad2)") (class "Default")
      (node (ref "R1-L2") (pin "2") (pinfunction "2_2") (pintype "passive"))
      (node (ref "T1-L2") (pin "B") (pinfunction "B_B") (pintype "passive"))
    )
    (net (code "36") (name "Net-(R1-L3-Pad2)") (class "Default")
      (node (ref "R1-L3") (pin "2") (pinfunction "2_2") (pintype "passive"))
      (node (ref "T1-L3") (pin "B") (pinfunction "B_B") (pintype "passive"))
    )
    (net (code "37") (name "Net-(R2-D0-Pad2)") (class "Default")
      (node (ref "R2-D0") (pin "2") (pinfunction "2_2") (pintype "passive"))
      (node (ref "T2-D0") (pin "B") (pinfunction "B_B") (pintype "passive"))
    )
    (net (code "38") (name "Net-(R2-D1-Pad2)") (class "Default")
      (node (ref "R2-D1") (pin "2") (pinfunction "2_2") (pintype "passive"))
      (node (ref "T2-D1") (pin "B") (pinfunction "B_B") (pintype "passive"))
    )
    (net (code "39") (name "Net-(R2-D2-Pad2)") (class "Default")
      (node (ref "R2-D2") (pin "2") (pinfunction "2_2") (pintype "passive"))
      (node (ref "T2-D2") (pin "B") (pinfunction "B_B") (pintype "passive"))
    )
    (net (code "40") (name "Net-(R2-D3-Pad2)") (class "Default")
      (node (ref "R2-D3") (pin "2") (pinfunction "2_2") (pintype "passive"))
      (node (ref "T2-D3") (pin "B") (pinfunction "B_B") (pintype "passive"))
    )
    (net (code "41") (name "Net-(R4-D0-Pad2)") (class "Default")
      (node (ref "R4-D0") (pin "2") (pinfunction "2_2") (pintype "passive"))
      (node (ref "T3-D0") (pin "B") (pinfunction "B_B") (pintype "passive"))
    )
    (net (code "42") (name "Net-(R4-D1-Pad2)") (class "Default")
      (node (ref "R4-D1") (pin "2") (pinfunction "2_2") (pintype "passive"))
      (node (ref "T3-D1") (pin "B") (pinfunction "B_B") (pintype "passive"))
    )
    (net (code "43") (name "Net-(R4-D2-Pad2)") (class "Default")
      (node (ref "R4-D2") (pin "2") (pinfunction "2_2") (pintype "passive"))
      (node (ref "T3-D2") (pin "B") (pinfunction "B_B") (pintype "passive"))
    )
    (net (code "44") (name "Net-(R4-D3-Pad2)") (class "Default")
      (node (ref "R4-D3") (pin "2") (pinfunction "2_2") (pintype "passive"))
      (node (ref "T3-D3") (pin "B") (pinfunction "B_B") (pintype "passive"))
    )
    (net (code "45") (name "Net-(R4-Pad2)") (class "Default")
      (node (ref "R4") (pin "2") (pinfunction "2_2") (pintype "passive"))
      (node (ref "T1") (pin "B") (pinfunction "B_B") (pintype "passive"))
    )
    (net (code "46") (name "Net-(R5-D0-Pad2)") (class "Default")
      (node (ref "R5-D0") (pin "2") (pinfunction "2_2") (pintype "passive"))
      (node (ref "R6-D0") (pin "1") (pinfunction "1_1") (pintype "passive"))
      (node (ref "T3-D0") (pin "E") (pinfunction "E_E") (pintype "passive"))
    )
    (net (code "47") (name "Net-(R5-D1-Pad2)") (class "Default")
      (node (ref "R5-D1") (pin "2") (pinfunction "2_2") (pintype "passive"))
      (node (ref "R6-D1") (pin "1") (pinfunction "1_1") (pintype "passive"))
      (node (ref "T3-D1") (pin "E") (pinfunction "E_E") (pintype "passive"))
    )
    (net (code "48") (name "Net-(R5-D2-Pad2)") (class "Default")
      (node (ref "R5-D2") (pin "2") (pinfunction "2_2") (pintype "passive"))
      (node (ref "R6-D2") (pin "1") (pinfunction "1_1") (pintype "passive"))
      (node (ref "T3-D2") (pin "E") (pinfunction "E_E") (pintype "passive"))
    )
    (net (code "49") (name "Net-(R5-D3-Pad2)") (class "Default")
      (node (ref "R5-D3") (pin "2") (pinfunction "2_2") (pintype "passive"))
      (node (ref "R6-D3") (pin "1") (pinfunction "1_1") (pintype "passive"))
      (node (ref "T3-D3") (pin "E") (pinfunction "E_E") (pintype "passive"))
    )
    (net (code "50") (name "Net-(R6-Pad2)") (class "Default")
      (node (ref "R6") (pin "2") (pinfunction "2_2") (pintype "passive"))
      (node (ref "T2") (pin "B") (pinfunction "B_B") (pintype "passive"))
    )
    (net (code "51") (name "Net-(R7-D0-Pad2)") (class "Default")
      (node (ref "R7-D0") (pin "2") (pinfunction "2_2") (pintype "passive"))
      (node (ref "T4-D0") (pin "B") (pinfunction "B_B") (pintype "passive"))
    )
    (net (code "52") (name "Net-(R7-D1-Pad2)") (class "Default")
      (node (ref "R7-D1") (pin "2") (pinfunction "2_2") (pintype "passive"))
      (node (ref "T4-D1") (pin "B") (pinfunction "B_B") (pintype "passive"))
    )
    (net (code "53") (name "Net-(R7-D2-Pad2)") (class "Default")
      (node (ref "R7-D2") (pin "2") (pinfunction "2_2") (pintype "passive"))
      (node (ref "T4-D2") (pin "B") (pinfunction "B_B") (pintype "passive"))
    )
    (net (code "54") (name "Net-(R7-D3-Pad2)") (class "Default")
      (node (ref "R7-D3") (pin "2") (pinfunction "2_2") (pintype "passive"))
      (node (ref "T4-D3") (pin "B") (pinfunction "B_B") (pintype "passive"))
    )
    (net (code "55") (name "Net-(R10-D0-Pad2)") (class "Default")
      (node (ref "R10-D0") (pin "2") (pinfunction "2_2") (pintype "passive"))
      (node (ref "R13-D0") (pin "2") (pinfunction "2_2") (pintype "passive"))
      (node (ref "T6-D0") (pin "B") (pinfunction "B_B") (pintype "passive"))
    )
    (net (code "56") (name "Net-(R10-D1-Pad2)") (class "Default")
      (node (ref "R10-D1") (pin "2") (pinfunction "2_2") (pintype "passive"))
      (node (ref "R13-D1") (pin "2") (pinfunction "2_2") (pintype "passive"))
      (node (ref "T6-D1") (pin "B") (pinfunction "B_B") (pintype "passive"))
    )
    (net (code "57") (name "Net-(R10-D2-Pad2)") (class "Default")
      (node (ref "R10-D2") (pin "2") (pinfunction "2_2") (pintype "passive"))
      (node (ref "R13-D2") (pin "2") (pinfunction "2_2") (pintype "passive"))
      (node (ref "T6-D2") (pin "B") (pinfunction "B_B") (pintype "passive"))
    )
    (net (code "58") (name "Net-(R10-D3-Pad2)") (class "Default")
      (node (ref "R10-D3") (pin "2") (pinfunction "2_2") (pintype "passive"))
      (node (ref "R13-D3") (pin "2") (pinfunction "2_2") (pintype "passive"))
      (node (ref "T6-D3") (pin "B") (pinfunction "B_B") (pintype "passive"))
    )
    (net (code "59") (name "Net-(R11-D0-Pad1)") (class "Default")
      (node (ref "R11-D0") (pin "1") (pinfunction "1_1") (pintype "passive"))
      (node (ref "R12-D0") (pin "2") (pinfunction "2_2") (pintype "passive"))
      (node (ref "T5-D0") (pin "B") (pinfunction "B_B") (pintype "passive"))
    )
    (net (code "60") (name "Net-(R11-D1-Pad1)") (class "Default")
      (node (ref "R11-D1") (pin "1") (pinfunction "1_1") (pintype "passive"))
      (node (ref "R12-D1") (pin "2") (pinfunction "2_2") (pintype "passive"))
      (node (ref "T5-D1") (pin "B") (pinfunction "B_B") (pintype "passive"))
    )
    (net (code "61") (name "Net-(R11-D2-Pad1)") (class "Default")
      (node (ref "R11-D2") (pin "1") (pinfunction "1_1") (pintype "passive"))
      (node (ref "R12-D2") (pin "2") (pinfunction "2_2") (pintype "passive"))
      (node (ref "T5-D2") (pin "B") (pinfunction "B_B") (pintype "passive"))
    )
    (net (code "62") (name "Net-(R11-D3-Pad1)") (class "Default")
      (node (ref "R11-D3") (pin "1") (pinfunction "1_1") (pintype "passive"))
      (node (ref "R12-D3") (pin "2") (pinfunction "2_2") (pintype "passive"))
      (node (ref "T5-D3") (pin "B") (pinfunction "B_B") (pintype "passive"))
    )
    (net (code "63") (name "Net-(R14-D0-Pad2)") (class "Default")
      (node (ref "R14-D0") (pin "2") (pinfunction "2_2") (pintype "passive"))
      (node (ref "T7-D0") (pin "B") (pinfunction "B_B") (pintype "passive"))
    )
    (net (code "64") (name "Net-(R14-D1-Pad2)") (class "Default")
      (node (ref "R14-D1") (pin "2") (pinfunction "2_2") (pintype "passive"))
      (node (ref "T7-D1") (pin "B") (pinfunction "B_B") (pintype "passive"))
    )
    (net (code "65") (name "Net-(R14-D2-Pad2)") (class "Default")
      (node (ref "R14-D2") (pin "2") (pinfunction "2_2") (pintype "passive"))
      (node (ref "T7-D2") (pin "B") (pinfunction "B_B") (pintype "passive"))
    )
    (net (code "66") (name "Net-(R14-D3-Pad2)") (class "Default")
      (node (ref "R14-D3") (pin "2") (pinfunction "2_2") (pintype "passive"))
      (node (ref "T7-D3") (pin "B") (pinfunction "B_B") (pintype "passive"))
    )
    (net (code "67") (name "Net-(R15-D0-Pad2)") (class "Default")
      (node (ref "R15-D0") (pin "2") (pinfunction "2_2") (pintype "passive"))
      (node (ref "T8-D0") (pin "B") (pinfunction "B_B") (pintype "passive"))
    )
    (net (code "68") (name "Net-(R15-D1-Pad2)") (class "Default")
      (node (ref "R15-D1") (pin "2") (pinfunction "2_2") (pintype "passive"))
      (node (ref "T8-D1") (pin "B") (pinfunction "B_B") (pintype "passive"))
    )
    (net (code "69") (name "Net-(R15-D2-Pad2)") (class "Default")
      (node (ref "R15-D2") (pin "2") (pinfunction "2_2") (pintype "passive"))
      (node (ref "T8-D2") (pin "B") (pinfunction "B_B") (pintype "passive"))
    )
    (net (code "70") (name "Net-(R15-D3-Pad2)") (class "Default")
      (node (ref "R15-D3") (pin "2") (pinfunction "2_2") (pintype "passive"))
      (node (ref "T8-D3") (pin "B") (pinfunction "B_B") (pintype "passive"))
    )
    (net (code "71") (name "Net-(R16-D0-Pad1)") (class "Default")
      (node (ref "R16-D0") (pin "1") (pinfunction "1_1") (pintype "passive"))
      (node (ref "T7-D0") (pin "C") (pinfunction "C_C") (pintype "passive"))
    )
    (net (code "72") (name "Net-(R31-Pad2)") (class "Default")
      (node (ref "R31") (pin "2") (pinfunction "2_2") (pintype "passive"))
      (node (ref "T15") (pin "B") (pinfunction "B_B") (pintype "passive"))
    )
    (net (code "73") (name "Net-(T1-D0-PadE)") (class "Default")
      (node (ref "T1-D0") (pin "E") (pinfunction "E_E") (pintype "passive"))
      (node (ref "T2-D0") (pin "C") (pinfunction "C_C") (pintype "passive"))
    )
    (net (code "74") (name "Net-(T1-D1-PadE)") (class "Default")
      (node (ref "T1-D1") (pin "E") (pinfunction "E_E") (pintype "passive"))
      (node (ref "T2-D1") (pin "C") (pinfunction "C_C") (pintype "passive"))
    )
    (net (code "75") (name "Net-(T1-D2-PadE)") (class "Default")
      (node (ref "T1-D2") (pin "E") (pinfunction "E_E") (pintype "passive"))
      (node (ref "T2-D2") (pin "C") (pinfunction "C_C") (pintype "passive"))
    )
    (net (code "76") (name "Net-(T1-D3-PadE)") (class "Default")
      (node (ref "T1-D3") (pin "E") (pinfunction "E_E") (pintype "passive"))
      (node (ref "T2-D3") (pin "C") (pinfunction "C_C") (pintype "passive"))
    )
    (net (code "77") (name "READ") (class "Default")
      (node (ref "R14-D0") (pin "1") (pinfunction "1_1") (pintype "passive"))
      (node (ref "R14-D1") (pin "1") (pinfunction "1_1") (pintype "passive"))
      (node (ref "R14-D2") (pin "1") (pinfunction "1_1") (pintype "passive"))
      (node (ref "R14-D3") (pin "1") (pinfunction "1_1") (pintype "passive"))
      (node (ref "R32") (pin "1") (pinfunction "1_1") (pintype "passive"))
      (node (ref "R6") (pin "1") (pinfunction "1_1") (pintype "passive"))
      (node (ref "T15") (pin "C") (pinfunction "C_C") (pintype "passive"))
    )
    (net (code "78") (name "RES-0") (class "Default")
      (node (ref "R13-D0") (pin "1") (pinfunction "1_1") (pintype "passive"))
      (node (ref "R6-D0") (pin "2") (pinfunction "2_2") (pintype "passive"))
      (node (ref "T4-D0") (pin "C") (pinfunction "C_C") (pintype "passive"))
    )
    (net (code "79") (name "RES-1") (class "Default")
      (node (ref "R13-D1") (pin "1") (pinfunction "1_1") (pintype "passive"))
      (node (ref "R6-D1") (pin "2") (pinfunction "2_2") (pintype "passive"))
      (node (ref "T4-D1") (pin "C") (pinfunction "C_C") (pintype "passive"))
    )
    (net (code "80") (name "RES-2") (class "Default")
      (node (ref "R13-D2") (pin "1") (pinfunction "1_1") (pintype "passive"))
      (node (ref "R6-D2") (pin "2") (pinfunction "2_2") (pintype "passive"))
      (node (ref "T4-D2") (pin "C") (pinfunction "C_C") (pintype "passive"))
    )
    (net (code "81") (name "RES-3") (class "Default")
      (node (ref "R13-D3") (pin "1") (pinfunction "1_1") (pintype "passive"))
      (node (ref "R6-D3") (pin "2") (pinfunction "2_2") (pintype "passive"))
      (node (ref "T4-D3") (pin "C") (pinfunction "C_C") (pintype "passive"))
    )
    (net (code "82") (name "SET-0") (class "Default")
      (node (ref "R12-D0") (pin "1") (pinfunction "1_1") (pintype "passive"))
      (node (ref "R3-D0") (pin "2") (pinfunction "2_2") (pintype "passive"))
      (node (ref "T2-D0") (pin "E") (pinfunction "E_E") (pintype "passive"))
    )
    (net (code "83") (name "SET-1") (class "Default")
      (node (ref "R12-D1") (pin "1") (pinfunction "1_1") (pintype "passive"))
      (node (ref "R3-D1") (pin "2") (pinfunction "2_2") (pintype "passive"))
      (node (ref "T2-D1") (pin "E") (pinfunction "E_E") (pintype "passive"))
    )
    (net (code "84") (name "SET-2") (class "Default")
      (node (ref "R12-D2") (pin "1") (pinfunction "1_1") (pintype "passive"))
      (node (ref "R3-D2") (pin "2") (pinfunction "2_2") (pintype "passive"))
      (node (ref "T2-D2") (pin "E") (pinfunction "E_E") (pintype "passive"))
    )
    (net (code "85") (name "SET-3") (class "Default")
      (node (ref "R12-D3") (pin "1") (pinfunction "1_1") (pintype "passive"))
      (node (ref "R3-D3") (pin "2") (pinfunction "2_2") (pintype "passive"))
      (node (ref "T2-D3") (pin "E") (pinfunction "E_E") (pintype "passive"))
    )
    (net (code "86") (name "WRITE") (class "Default")
      (node (ref "CTRL") (pin "2") (pinfunction "2_2") (pintype "passive"))
      (node (ref "R1") (pin "2") (pinfunction "2_2") (pintype "passive"))
      (node (ref "R2-D0") (pin "1") (pinfunction "1_1") (pintype "passive"))
      (node (ref "R2-D1") (pin "1") (pinfunction "1_1") (pintype "passive"))
      (node (ref "R2-D2") (pin "1") (pinfunction "1_1") (pintype "passive"))
      (node (ref "R2-D3") (pin "1") (pinfunction "1_1") (pintype "passive"))
      (node (ref "R4") (pin "1") (pinfunction "1_1") (pintype "passive"))
      (node (ref "R4-D0") (pin "1") (pinfunction "1_1") (pintype "passive"))
      (node (ref "R4-D1") (pin "1") (pinfunction "1_1") (pintype "passive"))
      (node (ref "R4-D2") (pin "1") (pinfunction "1_1") (pintype "passive"))
      (node (ref "R4-D3") (pin "1") (pinfunction "1_1") (pintype "passive"))
    )
    (net (code "87") (name "{slash}D1") (class "Default")
      (node (ref "R10-D1") (pin "1") (pinfunction "1_1") (pintype "passive"))
      (node (ref "R15-D1") (pin "1") (pinfunction "1_1") (pintype "passive"))
      (node (ref "R8-D1") (pin "1") (pinfunction "1_1") (pintype "passive"))
      (node (ref "T5-D1") (pin "C") (pinfunction "C_C") (pintype "passive"))
    )
    (net (code "88") (name "{slash}D2") (class "Default")
      (node (ref "R10-D2") (pin "1") (pinfunction "1_1") (pintype "passive"))
      (node (ref "R15-D2") (pin "1") (pinfunction "1_1") (pintype "passive"))
      (node (ref "R8-D2") (pin "1") (pinfunction "1_1") (pintype "passive"))
      (node (ref "T5-D2") (pin "C") (pinfunction "C_C") (pintype "passive"))
    )
    (net (code "89") (name "{slash}D3") (class "Default")
      (node (ref "R10-D3") (pin "1") (pinfunction "1_1") (pintype "passive"))
      (node (ref "R15-D3") (pin "1") (pinfunction "1_1") (pintype "passive"))
      (node (ref "R8-D3") (pin "1") (pinfunction "1_1") (pintype "passive"))
      (node (ref "T5-D3") (pin "C") (pinfunction "C_C") (pintype "passive"))
    )
  )
)
